# main.net
KiCad netlist of a schematic drawn in Altium Designer
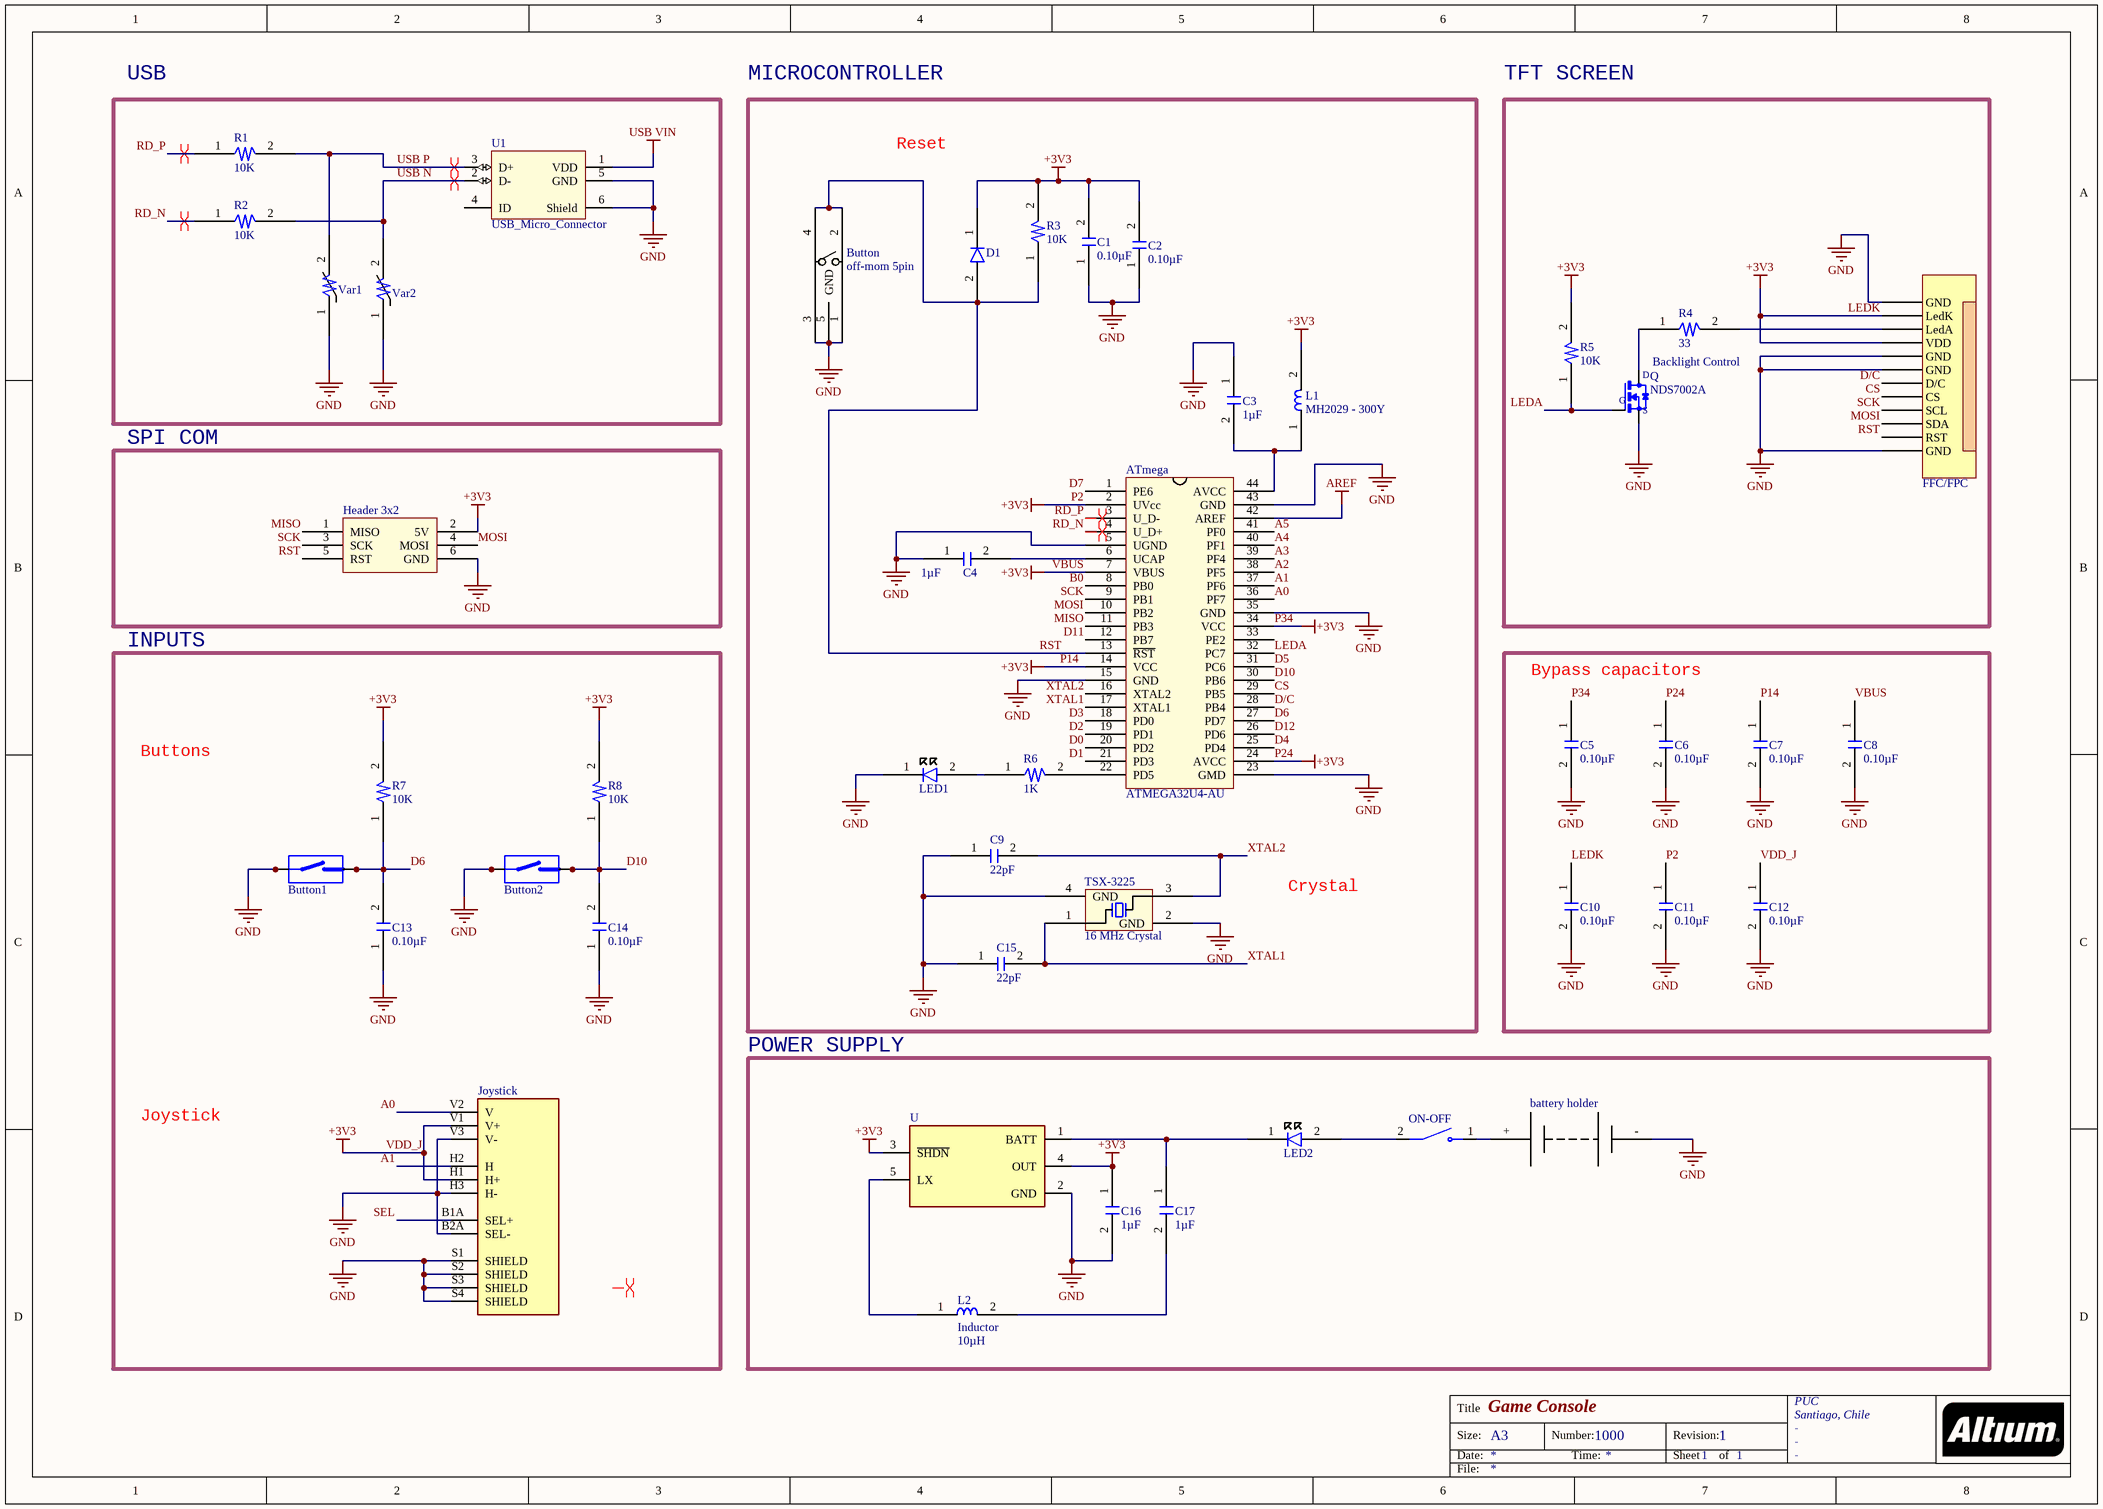
[diagram p0: main.SchDoc]

(export (version "E")
  (design (tool "Eeschema 10.0.6"))
  (components
    (comp (ref "ATmega")
      (value "ATmega32u4")
      (footprint "ATmega32u4_TQFP44")
      (fields (field (name "SUPPLIER PART NUMBER 1") "ATMEGA32U4-AU"))
      (libsource (lib "Schlib1") (part "ATmega32U4"))
    )
    (comp (ref "battery holder") (value "battery holder") (libsource (lib "Schlib1") (part "BCAAPC")))
    (comp (ref "Button")
      (value "off-mom 5pin")
      (footprint "450-1760")
      (libsource (lib "Schlib1") (part "Button"))
    )
    (comp (ref "Button1")
      (value "5-1437565-0")
      (footprint "SnapEDApcb:SW_5-1437565-0")
      (description "Switch Push Button N.O. SPST Round Button 0.05A 12VDC 1VA Alternate Contact Gull Wing SMD T/R")
      (fields (field (name "MP") "FSM6JSMATR") (field (name "MF") "TE Connectivity"))
      (libsource (lib "Schlib1") (part "5-1437565-0"))
    )
    (comp (ref "Button2")
      (value "5-1437565-0")
      (footprint "SnapEDApcb:SW_5-1437565-0")
      (description "Switch Push Button N.O. SPST Round Button 0.05A 12VDC 1VA Alternate Contact Gull Wing SMD T/R")
      (fields (field (name "MP") "FSM6JSMATR") (field (name "MF") "TE Connectivity"))
      (libsource (lib "Schlib1") (part "5-1437565-0"))
    )
    (comp (ref "C1")
      (value "0.10µF")
      (footprint "R15_0805_cap_M")
      (fields (field (name "Comment") "0.10µ 25V"))
      (libsource (lib "Schlib1") (part "0.10µF 25V Cap"))
    )
    (comp (ref "C2")
      (value "0.10µF")
      (footprint "R15_0805_cap_M")
      (fields (field (name "Comment") "0.10µ 25V"))
      (libsource (lib "Schlib1") (part "0.10µF 25V Cap"))
    )
    (comp (ref "C3")
      (value "1µF")
      (footprint "C2012_M")
      (fields (field (name "Comment") "1µF 50V cap"))
      (libsource (lib "Schlib1") (part "1µF 50V cap"))
    )
    (comp (ref "C4")
      (value "1µF")
      (footprint "C2012_M")
      (fields (field (name "Comment") "1µF 50V cap"))
      (libsource (lib "Schlib1") (part "1µF 50V cap"))
    )
    (comp (ref "C5")
      (value "0.10µF")
      (footprint "R15_0805_cap_M")
      (fields (field (name "Comment") "0.10µ 25V"))
      (libsource (lib "Schlib1") (part "0.10µF 25V Cap"))
    )
    (comp (ref "C6")
      (value "0.10µF")
      (footprint "R15_0805_cap_M")
      (fields (field (name "Comment") "0.10µ 25V"))
      (libsource (lib "Schlib1") (part "0.10µF 25V Cap"))
    )
    (comp (ref "C7")
      (value "0.10µF")
      (footprint "R15_0805_cap_M")
      (fields (field (name "Comment") "0.10µ 25V"))
      (libsource (lib "Schlib1") (part "0.10µF 25V Cap"))
    )
    (comp (ref "C8")
      (value "0.10µF")
      (footprint "R15_0805_cap_M")
      (fields (field (name "Comment") "0.10µ 25V"))
      (libsource (lib "Schlib1") (part "0.10µF 25V Cap"))
    )
    (comp (ref "C9")
      (value "22pF")
      (footprint "R15_0805_cap_M")
      (fields (field (name "Comment") "22pF 50V cap"))
      (libsource (lib "Schlib1") (part "22pF 50V cap"))
    )
    (comp (ref "C10")
      (value "0.10µF")
      (footprint "R15_0805_cap_M")
      (fields (field (name "Comment") "0.10µ 25V"))
      (libsource (lib "Schlib1") (part "0.10µF 25V Cap"))
    )
    (comp (ref "C11")
      (value "0.10µF")
      (footprint "R15_0805_cap_M")
      (fields (field (name "Comment") "0.10µ 25V"))
      (libsource (lib "Schlib1") (part "0.10µF 25V Cap"))
    )
    (comp (ref "C12")
      (value "0.10µF")
      (footprint "R15_0805_cap_M")
      (fields (field (name "Comment") "0.10µ 25V"))
      (libsource (lib "Schlib1") (part "0.10µF 25V Cap"))
    )
    (comp (ref "C13")
      (value "0.10µF")
      (footprint "R15_0805_cap_M")
      (fields (field (name "Comment") "0.10µ 25V"))
      (libsource (lib "Schlib1") (part "0.10µF 25V Cap"))
    )
    (comp (ref "C14")
      (value "0.10µF")
      (footprint "R15_0805_cap_M")
      (fields (field (name "Comment") "0.10µ 25V"))
      (libsource (lib "Schlib1") (part "0.10µF 25V Cap"))
    )
    (comp (ref "C15")
      (value "22pF")
      (footprint "R15_0805_cap_M")
      (fields (field (name "Comment") "22pF 50V cap"))
      (libsource (lib "Schlib1") (part "22pF 50V cap"))
    )
    (comp (ref "C16")
      (value "1µF")
      (footprint "C2012_M")
      (fields (field (name "Comment") "1µF 50V cap"))
      (libsource (lib "Schlib1") (part "1µF 50V cap"))
    )
    (comp (ref "C17")
      (value "1µF")
      (footprint "C2012_M")
      (fields (field (name "Comment") "1µF 50V cap"))
      (libsource (lib "Schlib1") (part "1µF 50V cap"))
    )
    (comp (ref "D1")
      (value "100V Switching Diode")
      (footprint "C2012_M")
      (description "Standard Diode")
      (libsource (lib "Schlib1") (part "CD1206 - S01575"))
    )
    (comp (ref "FFC/FPC") (value "1-84952-2") (libsource (lib "Schlib1") (part "1-84952-2")))
    (comp (ref "Header 3x2")
      (value "J3*2")
      (footprint "J3*2")
      (description "Header 3*2")
      (libsource (lib "Schlib1") (part "J3*2"))
    )
    (comp (ref "Joystick")
      (value "COM-09032")
      (footprint "SnapEDApcb:XDCR_COM-09032")
      (description "Joystick, 2 - Axis Analog _Resistive_ Output")
      (fields (field (name "MF") "SparkFun Electronics"))
      (libsource (lib "Schlib1") (part "COM-09032"))
    )
    (comp (ref "L1")
      (value "MH2029 - 300Y")
      (footprint "MH2029-300YC")
      (description "Ferrite bead")
      (libsource (lib "Schlib1") (part "MH2029 - 300Y"))
    )
    (comp (ref "L2")
      (value "Inductor")
      (footprint "MH2029-300YC")
      (fields (field (name "ALTIUM_VALUE") "10µH"))
      (libsource (lib "Schlib1") (part "Inductor"))
    )
    (comp (ref "LED1")
      (value "LED")
      (footprint "Wurth led 0805")
      (description "LED 0805")
      (libsource (lib "Schlib1") (part "LED"))
    )
    (comp (ref "LED2")
      (value "LED")
      (footprint "Wurth led 0805")
      (description "LED 0805")
      (libsource (lib "Schlib1") (part "LED"))
    )
    (comp (ref "ON-OFF")
      (value "RB141C1100")
      (footprint "SnapEDApcb:SW_RB141C1100")
      (description "Rocker Switch SPST 15A _AC_ 125V Panel Mount, Snap-In")
      (fields (field (name "MF") "E-Switch"))
      (libsource (lib "Schlib1") (part "RB141C1100"))
    )
    (comp (ref "Q")
      (value "NDS7002A")
      (footprint "SOT23")
      (description "N-Channel 60V 280mA _Ta_ 300mW _Ta_ Surface Mount SOT-23 _TO-236AB_")
      (fields (field (name "MF") "ON Semiconductor"))
      (libsource (lib "NDS7002A") (part "NDS7002A"))
    )
    (comp (ref "R1")
      (value "10K")
      (footprint "RNCP0805_M")
      (description "Resistor 0805")
      (fields (field (name "Comment") "Res"))
      (libsource (lib "Schlib1") (part "10k Res_1"))
    )
    (comp (ref "R2")
      (value "10K")
      (footprint "RNCP0805_M")
      (description "Resistor 0805")
      (fields (field (name "Comment") "Res"))
      (libsource (lib "Schlib1") (part "10k Res_1"))
    )
    (comp (ref "R3")
      (value "10K")
      (footprint "RNCP0805_M")
      (description "Resistor 0805")
      (fields (field (name "Comment") "Res"))
      (libsource (lib "Schlib1") (part "10k Res"))
    )
    (comp (ref "R4")
      (value "33")
      (footprint "RNCP0805_M")
      (description "Resistor 0805")
      (fields (field (name "Comment") "Res"))
      (libsource (lib "Schlib1") (part "33 Res_1"))
    )
    (comp (ref "R5")
      (value "10K")
      (footprint "RNCP0805_M")
      (description "Resistor 0805")
      (fields (field (name "Comment") "Res"))
      (libsource (lib "Schlib1") (part "10k Res"))
    )
    (comp (ref "R6")
      (value "1K")
      (footprint "RNCP0805_M")
      (description "Resistor 0805")
      (fields (field (name "Comment") "Res"))
      (libsource (lib "Schlib1") (part "1k Res"))
    )
    (comp (ref "R7")
      (value "10K")
      (footprint "RNCP0805_M")
      (description "Resistor 0805")
      (fields (field (name "Comment") "Res"))
      (libsource (lib "Schlib1") (part "10k Res"))
    )
    (comp (ref "R8")
      (value "10K")
      (footprint "RNCP0805_M")
      (description "Resistor 0805")
      (fields (field (name "Comment") "Res"))
      (libsource (lib "Schlib1") (part "10k Res"))
    )
    (comp (ref "TSX-3225")
      (value "16 MHz Crystal")
      (footprint "TSX-3225")
      (libsource (lib "Schlib1") (part "16 MHz Crystal"))
    )
    (comp (ref "U")
      (value "MAX1724EZK33+T")
      (footprint "SnapEDApcb:SOT95P275X110-5N")
      (description "Boost Switching Regulator IC Positive Fixed 3.3V 1 Output 400mA _Switch_ SOT-23-5 Thin, TSOT-23-5")
      (fields (field (name "MF") "Maxim Integrated"))
      (libsource (lib "Schlib1") (part "MAX1724EZK33+T"))
    )
    (comp (ref "U1")
      (value "USB_Micro_Connector")
      (footprint "USB_micro_through")
      (description "CONN USB MICRO B RECPT SMT R/A")
      (fields
        (field (name "MANUFACTURER PART NUMBER") "10118194-0001LF")
        (field (name "01 CREATED BY") "David Lynch @ 30/11/2017")
        (field (name "02 REVIEWED BY") "Rodrigo Maureira @ 14/01/2018")
      )
      (libsource (lib "Schlib1") (part "USB_micro_through"))
    )
    (comp (ref "Var1")
      (value "Gard Resistor")
      (footprint "UltraGuard 0805")
      (libsource (lib "Schlib1") (part "Gard Resistor"))
    )
    (comp (ref "Var2")
      (value "Gard Resistor")
      (footprint "UltraGuard 0805")
      (libsource (lib "Schlib1") (part "Gard Resistor"))
    )
  )
  (nets
    (net (code "1") (name "+3V3") (class "Default")
      (node (ref "ATmega") (pin "14") (pinfunction "VCC_14") (pintype "passive"))
      (node (ref "ATmega") (pin "2") (pinfunction "UVcc_2") (pintype "passive"))
      (node (ref "ATmega") (pin "24") (pinfunction "AVCC_24") (pintype "passive"))
      (node (ref "ATmega") (pin "34") (pinfunction "VCC_34") (pintype "passive"))
      (node (ref "ATmega") (pin "7") (pinfunction "VBUS_7") (pintype "passive"))
      (node (ref "C1") (pin "2") (pinfunction "2_2") (pintype "passive"))
      (node (ref "C10") (pin "1") (pinfunction "1_1") (pintype "passive"))
      (node (ref "C11") (pin "1") (pinfunction "1_1") (pintype "passive"))
      (node (ref "C12") (pin "1") (pinfunction "1_1") (pintype "passive"))
      (node (ref "C16") (pin "1") (pinfunction "1_1") (pintype "passive"))
      (node (ref "C2") (pin "2") (pinfunction "2_2") (pintype "passive"))
      (node (ref "C5") (pin "1") (pinfunction "1_1") (pintype "passive"))
      (node (ref "C6") (pin "1") (pinfunction "1_1") (pintype "passive"))
      (node (ref "C7") (pin "1") (pinfunction "1_1") (pintype "passive"))
      (node (ref "C8") (pin "1") (pinfunction "1_1") (pintype "passive"))
      (node (ref "D1") (pin "1") (pinfunction "1_1") (pintype "passive"))
      (node (ref "FFC/FPC") (pin "10") (pinfunction "VDD_10") (pintype "passive"))
      (node (ref "FFC/FPC") (pin "2") (pinfunction "LedK_2") (pintype "passive"))
      (node (ref "Header 3x2") (pin "2") (pinfunction "5V_2") (pintype "passive"))
      (node (ref "Joystick") (pin "H1") (pinfunction "H+_H1") (pintype "passive"))
      (node (ref "Joystick") (pin "V1") (pinfunction "V+_V1") (pintype "passive"))
      (node (ref "L1") (pin "2") (pinfunction "2_2") (pintype "passive"))
      (node (ref "R3") (pin "2") (pinfunction "2_2") (pintype "passive"))
      (node (ref "R5") (pin "2") (pinfunction "2_2") (pintype "passive"))
      (node (ref "R7") (pin "2") (pinfunction "2_2") (pintype "passive"))
      (node (ref "R8") (pin "2") (pinfunction "2_2") (pintype "passive"))
      (node (ref "U") (pin "3") (pinfunction "~{SHDN}_3") (pintype "passive"))
      (node (ref "U") (pin "4") (pinfunction "OUT_4") (pintype "passive"))
    )
    (net (code "2") (name "/A0") (class "Default")
      (node (ref "ATmega") (pin "36") (pinfunction "PF7_36") (pintype "passive"))
      (node (ref "Joystick") (pin "V2") (pinfunction "V_V2") (pintype "passive"))
    )
    (net (code "3") (name "/A1") (class "Default")
      (node (ref "ATmega") (pin "37") (pinfunction "PF6_37") (pintype "passive"))
      (node (ref "Joystick") (pin "H2") (pinfunction "H_H2") (pintype "passive"))
    )
    (net (code "4") (name "/A2") (class "Default")
      (node (ref "ATmega") (pin "38") (pinfunction "PF5_38") (pintype "passive"))
    )
    (net (code "5") (name "/A3") (class "Default")
      (node (ref "ATmega") (pin "39") (pinfunction "PF4_39") (pintype "passive"))
    )
    (net (code "6") (name "/A4") (class "Default")
      (node (ref "ATmega") (pin "40") (pinfunction "PF1_40") (pintype "passive"))
    )
    (net (code "7") (name "/A5") (class "Default")
      (node (ref "ATmega") (pin "41") (pinfunction "PF0_41") (pintype "passive"))
    )
    (net (code "8") (name "/B0") (class "Default")
      (node (ref "ATmega") (pin "8") (pinfunction "PB0_8") (pintype "passive"))
    )
    (net (code "9") (name "/CS") (class "Default")
      (node (ref "ATmega") (pin "29") (pinfunction "PB5_29") (pintype "passive"))
      (node (ref "FFC/FPC") (pin "8") (pinfunction "CS_8") (pintype "passive"))
    )
    (net (code "10") (name "/D0") (class "Default")
      (node (ref "ATmega") (pin "20") (pinfunction "PD2_20") (pintype "passive"))
    )
    (net (code "11") (name "/D1") (class "Default")
      (node (ref "ATmega") (pin "21") (pinfunction "PD3_21") (pintype "passive"))
    )
    (net (code "12") (name "/D2") (class "Default")
      (node (ref "ATmega") (pin "19") (pinfunction "PD1_19") (pintype "passive"))
    )
    (net (code "13") (name "/D3") (class "Default")
      (node (ref "ATmega") (pin "18") (pinfunction "PD0_18") (pintype "passive"))
    )
    (net (code "14") (name "/D4") (class "Default")
      (node (ref "ATmega") (pin "25") (pinfunction "PD4_25") (pintype "passive"))
    )
    (net (code "15") (name "/D5") (class "Default")
      (node (ref "ATmega") (pin "31") (pinfunction "PC6_31") (pintype "passive"))
    )
    (net (code "16") (name "/D6") (class "Default")
      (node (ref "ATmega") (pin "27") (pinfunction "PD7_27") (pintype "passive"))
      (node (ref "Button1") (pin "1") (pinfunction "2_1") (pintype "passive"))
      (node (ref "Button1") (pin "2") (pinfunction "2_2") (pintype "passive"))
      (node (ref "C13") (pin "2") (pinfunction "2_2") (pintype "passive"))
      (node (ref "R7") (pin "1") (pinfunction "1_1") (pintype "passive"))
    )
    (net (code "17") (name "/D7") (class "Default")
      (node (ref "ATmega") (pin "1") (pinfunction "PE6_1") (pintype "passive"))
    )
    (net (code "18") (name "/D10") (class "Default")
      (node (ref "ATmega") (pin "30") (pinfunction "PB6_30") (pintype "passive"))
      (node (ref "Button2") (pin "1") (pinfunction "2_1") (pintype "passive"))
      (node (ref "Button2") (pin "2") (pinfunction "2_2") (pintype "passive"))
      (node (ref "C14") (pin "2") (pinfunction "2_2") (pintype "passive"))
      (node (ref "R8") (pin "1") (pinfunction "1_1") (pintype "passive"))
    )
    (net (code "19") (name "/D11") (class "Default")
      (node (ref "ATmega") (pin "12") (pinfunction "PB7_12") (pintype "passive"))
    )
    (net (code "20") (name "/D12") (class "Default")
      (node (ref "ATmega") (pin "26") (pinfunction "PD6_26") (pintype "passive"))
    )
    (net (code "21") (name "/D{slash}C") (class "Default")
      (node (ref "ATmega") (pin "28") (pinfunction "PB4_28") (pintype "passive"))
      (node (ref "FFC/FPC") (pin "7") (pinfunction "D/C_7") (pintype "passive"))
    )
    (net (code "22") (name "/LEDA") (class "Default")
      (node (ref "ATmega") (pin "32") (pinfunction "PC7_32") (pintype "passive"))
      (node (ref "Q") (pin "1") (pinfunction "G_1") (pintype "passive"))
      (node (ref "R5") (pin "1") (pinfunction "1_1") (pintype "passive"))
    )
    (net (code "23") (name "/MISO") (class "Default")
      (node (ref "ATmega") (pin "11") (pinfunction "PB3_11") (pintype "passive"))
      (node (ref "Header 3x2") (pin "1") (pinfunction "MISO_1") (pintype "passive"))
    )
    (net (code "24") (name "/MOSI") (class "Default")
      (node (ref "ATmega") (pin "10") (pinfunction "PB2_10") (pintype "passive"))
      (node (ref "FFC/FPC") (pin "10") (pinfunction "SDA_10") (pintype "passive"))
      (node (ref "Header 3x2") (pin "4") (pinfunction "MOSI_4") (pintype "passive"))
    )
    (net (code "25") (name "/RD_N") (class "Default")
      (node (ref "ATmega") (pin "4") (pinfunction "U_D+_4") (pintype "passive"))
      (node (ref "R2") (pin "1") (pinfunction "1_1") (pintype "passive"))
    )
    (net (code "26") (name "/RD_P") (class "Default")
      (node (ref "ATmega") (pin "3") (pinfunction "U_D-_3") (pintype "passive"))
      (node (ref "R1") (pin "1") (pinfunction "1_1") (pintype "passive"))
    )
    (net (code "27") (name "/RST") (class "Default")
      (node (ref "ATmega") (pin "13") (pinfunction "~{RST}_13") (pintype "passive"))
      (node (ref "Button") (pin "2") (pinfunction "2_2") (pintype "passive"))
      (node (ref "Button") (pin "4") (pinfunction "4_4") (pintype "passive"))
      (node (ref "D1") (pin "2") (pinfunction "2_2") (pintype "passive"))
      (node (ref "FFC/FPC") (pin "11") (pinfunction "RST_11") (pintype "passive"))
      (node (ref "Header 3x2") (pin "5") (pinfunction "RST_5") (pintype "passive"))
      (node (ref "R3") (pin "1") (pinfunction "1_1") (pintype "passive"))
    )
    (net (code "28") (name "/SCK") (class "Default")
      (node (ref "ATmega") (pin "9") (pinfunction "PB1_9") (pintype "passive"))
      (node (ref "FFC/FPC") (pin "9") (pinfunction "SCL_9") (pintype "passive"))
      (node (ref "Header 3x2") (pin "3") (pinfunction "SCK_3") (pintype "passive"))
    )
    (net (code "29") (name "/SEL") (class "Default")
      (node (ref "Joystick") (pin "B1A") (pinfunction "SEL+_B1A") (pintype "passive"))
    )
    (net (code "30") (name "/USB N") (class "Default")
      (node (ref "R2") (pin "2") (pinfunction "2_2") (pintype "passive"))
      (node (ref "U1") (pin "2") (pinfunction "D-_2") (pintype "bidirectional"))
      (node (ref "Var2") (pin "2") (pinfunction "2_2") (pintype "passive"))
    )
    (net (code "31") (name "/USB P") (class "Default")
      (node (ref "R1") (pin "2") (pinfunction "2_2") (pintype "passive"))
      (node (ref "U1") (pin "3") (pinfunction "D+_3") (pintype "bidirectional"))
      (node (ref "Var1") (pin "2") (pinfunction "2_2") (pintype "passive"))
    )
    (net (code "32") (name "/XTAL1") (class "Default")
      (node (ref "ATmega") (pin "17") (pinfunction "XTAL1_17") (pintype "passive"))
      (node (ref "C15") (pin "2") (pinfunction "2_2") (pintype "passive"))
      (node (ref "TSX-3225") (pin "1") (pinfunction "1_1") (pintype "passive"))
    )
    (net (code "33") (name "/XTAL2") (class "Default")
      (node (ref "ATmega") (pin "16") (pinfunction "XTAL2_16") (pintype "passive"))
      (node (ref "C9") (pin "2") (pinfunction "2_2") (pintype "passive"))
      (node (ref "TSX-3225") (pin "3") (pinfunction "3_3") (pintype "passive"))
    )
    (net (code "34") (name "AREF") (class "Default")
      (node (ref "ATmega") (pin "42") (pinfunction "AREF_42") (pintype "passive"))
    )
    (net (code "35") (name "GND") (class "Default")
      (node (ref "ATmega") (pin "15") (pinfunction "GND_15") (pintype "passive"))
      (node (ref "ATmega") (pin "23") (pinfunction "GMD_23") (pintype "passive"))
      (node (ref "ATmega") (pin "35") (pinfunction "GND_35") (pintype "passive"))
      (node (ref "ATmega") (pin "43") (pinfunction "GND_43") (pintype "passive"))
      (node (ref "ATmega") (pin "5") (pinfunction "UGND_5") (pintype "passive"))
      (node (ref "Button") (pin "1") (pinfunction "1_1") (pintype "passive"))
      (node (ref "Button") (pin "3") (pinfunction "3_3") (pintype "passive"))
      (node (ref "Button") (pin "5") (pinfunction "GND_5") (pintype "passive"))
      (node (ref "Button1") (pin "3") (pinfunction "1_3") (pintype "passive"))
      (node (ref "Button1") (pin "4") (pinfunction "1_4") (pintype "passive"))
      (node (ref "Button2") (pin "3") (pinfunction "1_3") (pintype "passive"))
      (node (ref "Button2") (pin "4") (pinfunction "1_4") (pintype "passive"))
      (node (ref "C1") (pin "1") (pinfunction "1_1") (pintype "passive"))
      (node (ref "C10") (pin "2") (pinfunction "2_2") (pintype "passive"))
      (node (ref "C11") (pin "2") (pinfunction "2_2") (pintype "passive"))
      (node (ref "C12") (pin "2") (pinfunction "2_2") (pintype "passive"))
      (node (ref "C13") (pin "1") (pinfunction "1_1") (pintype "passive"))
      (node (ref "C14") (pin "1") (pinfunction "1_1") (pintype "passive"))
      (node (ref "C15") (pin "1") (pinfunction "1_1") (pintype "passive"))
      (node (ref "C16") (pin "2") (pinfunction "2_2") (pintype "passive"))
      (node (ref "C2") (pin "1") (pinfunction "1_1") (pintype "passive"))
      (node (ref "C3") (pin "1") (pinfunction "1_1") (pintype "passive"))
      (node (ref "C4") (pin "1") (pinfunction "1_1") (pintype "passive"))
      (node (ref "C5") (pin "2") (pinfunction "2_2") (pintype "passive"))
      (node (ref "C6") (pin "2") (pinfunction "2_2") (pintype "passive"))
      (node (ref "C7") (pin "2") (pinfunction "2_2") (pintype "passive"))
      (node (ref "C8") (pin "2") (pinfunction "2_2") (pintype "passive"))
      (node (ref "C9") (pin "1") (pinfunction "1_1") (pintype "passive"))
      (node (ref "FFC/FPC") (pin "1") (pinfunction "GND_1") (pintype "passive"))
      (node (ref "FFC/FPC") (pin "12") (pinfunction "GND_12") (pintype "passive"))
      (node (ref "FFC/FPC") (pin "5") (pinfunction "GND_5") (pintype "passive"))
      (node (ref "FFC/FPC") (pin "6") (pinfunction "GND_6") (pintype "passive"))
      (node (ref "Header 3x2") (pin "6") (pinfunction "GND_6") (pintype "passive"))
      (node (ref "Joystick") (pin "B2A") (pinfunction "SEL-_B2A") (pintype "passive"))
      (node (ref "Joystick") (pin "H3") (pinfunction "H-_H3") (pintype "passive"))
      (node (ref "Joystick") (pin "S1") (pinfunction "SHIELD_S1") (pintype "passive"))
      (node (ref "Joystick") (pin "S2") (pinfunction "SHIELD_S2") (pintype "passive"))
      (node (ref "Joystick") (pin "S3") (pinfunction "SHIELD_S3") (pintype "passive"))
      (node (ref "Joystick") (pin "S4") (pinfunction "SHIELD_S4") (pintype "passive"))
      (node (ref "Joystick") (pin "V3") (pinfunction "V-_V3") (pintype "passive"))
      (node (ref "LED1") (pin "1") (pinfunction "1_1") (pintype "passive"))
      (node (ref "Q") (pin "2") (pinfunction "S_2") (pintype "passive"))
      (node (ref "TSX-3225") (pin "2") (pinfunction "GND_2") (pintype "passive"))
      (node (ref "TSX-3225") (pin "4") (pinfunction "GND_4") (pintype "passive"))
      (node (ref "U") (pin "2") (pinfunction "GND_2") (pintype "power_in"))
      (node (ref "U1") (pin "5") (pinfunction "GND_5") (pintype "power_in"))
      (node (ref "U1") (pin "6") (pinfunction "Shield_6") (pintype "passive"))
      (node (ref "Var1") (pin "1") (pinfunction "1_1") (pintype "passive"))
      (node (ref "Var2") (pin "1") (pinfunction "1_1") (pintype "passive"))
    )
    (net (code "36") (name "Net-(ATmega-AVCC-Pad44)") (class "Default")
      (node (ref "ATmega") (pin "44") (pinfunction "AVCC_44") (pintype "passive"))
      (node (ref "C3") (pin "2") (pinfunction "2_2") (pintype "passive"))
      (node (ref "L1") (pin "1") (pinfunction "1_1") (pintype "passive"))
    )
    (net (code "37") (name "Net-(ATmega-PD5)") (class "Default")
      (node (ref "ATmega") (pin "22") (pinfunction "PD5_22") (pintype "passive"))
      (node (ref "R6") (pin "2") (pinfunction "2_2") (pintype "passive"))
    )
    (net (code "38") (name "Net-(ATmega-UCAP)") (class "Default")
      (node (ref "ATmega") (pin "6") (pinfunction "UCAP_6") (pintype "passive"))
      (node (ref "C4") (pin "2") (pinfunction "2_2") (pintype "passive"))
    )
    (net (code "39") (name "Net-(C17-Pad2)") (class "Default")
      (node (ref "C17") (pin "2") (pinfunction "2_2") (pintype "passive"))
      (node (ref "L2") (pin "2") (pinfunction "2_2") (pintype "passive"))
    )
    (net (code "40") (name "Net-(FFC/FPC-LedA)") (class "Default")
      (node (ref "FFC/FPC") (pin "3") (pinfunction "LedA_3") (pintype "passive"))
      (node (ref "R4") (pin "2") (pinfunction "2_2") (pintype "passive"))
    )
    (net (code "41") (name "Net-(LED1-Pad2)") (class "Default")
      (node (ref "LED1") (pin "2") (pinfunction "2_2") (pintype "passive"))
      (node (ref "R6") (pin "1") (pinfunction "1_1") (pintype "passive"))
    )
    (net (code "42") (name "Net-(LED2-Pad2)") (class "Default")
      (node (ref "LED2") (pin "2") (pinfunction "2_2") (pintype "passive"))
      (node (ref "ON-OFF") (pin "2") (pinfunction "2_2") (pintype "passive"))
    )
    (net (code "43") (name "Net-(Q-D)") (class "Default")
      (node (ref "Q") (pin "3") (pinfunction "D_3") (pintype "passive"))
      (node (ref "R4") (pin "1") (pinfunction "1_1") (pintype "passive"))
    )
    (net (code "44") (name "Net-(U-BATT)") (class "Default")
      (node (ref "C17") (pin "1") (pinfunction "1_1") (pintype "passive"))
      (node (ref "LED2") (pin "1") (pinfunction "1_1") (pintype "passive"))
      (node (ref "U") (pin "1") (pinfunction "BATT_1") (pintype "power_in"))
    )
    (net (code "45") (name "Net-(U-LX)") (class "Default")
      (node (ref "L2") (pin "1") (pinfunction "1_1") (pintype "passive"))
      (node (ref "U") (pin "5") (pinfunction "LX_5") (pintype "passive"))
    )
    (net (code "46") (name "USB VIN") (class "Default")
      (node (ref "U1") (pin "1") (pinfunction "VDD_1") (pintype "power_in"))
    )
    (net (code "47") (name "unconnected-(ATmega-PE2-Pad33)") (class "Default")
      (node (ref "ATmega") (pin "33") (pinfunction "PE2_33") (pintype "passive"))
    )
    (net (code "48") (name "unconnected-(ON-OFF-Pad1)") (class "Default")
      (node (ref "ON-OFF") (pin "1") (pinfunction "1_1") (pintype "passive"))
    )
    (net (code "49") (name "unconnected-(U1-ID-Pad4)") (class "Default")
      (node (ref "U1") (pin "4") (pinfunction "ID_4") (pintype "passive"))
    )
    (net (code "50") (name "unconnected-(battery holder-Pad+)") (class "Default")
      (node (ref "battery holder") (pin "+") (pinfunction "+_+") (pintype "passive"))
    )
    (net (code "51") (name "unconnected-(battery holder-Pad-)") (class "Default")
      (node (ref "battery holder") (pin "-") (pinfunction "-_-") (pintype "passive"))
    )
  )
)
